# ContDet.net
KiCad netlist of a schematic drawn in EAGLE
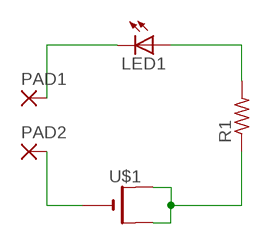
[diagram p0: schematic, sheet 1]

(export (version "E")
  (design (tool "Eeschema 10.0.6"))
  (components
    (comp (ref "LED1")
      (value "LEDCHIPLED_0805")
      (footprint "eagle-import:CHIPLED_0805")
      (libsource (lib "eagle-import") (part "LEDCHIPLED_0805"))
    )
    (comp (ref "PAD1")
      (value "SMD2")
      (footprint "eagle-import:SMD1,27-2,54")
      (libsource (lib "eagle-import") (part "SMD2"))
    )
    (comp (ref "PAD2")
      (value "SMD2")
      (footprint "eagle-import:SMD1,27-2,54")
      (libsource (lib "eagle-import") (part "SMD2"))
    )
    (comp (ref "R1")
      (value "R-US_FLIPFLOP")
      (footprint "eagle-import:0805-THM")
      (libsource (lib "eagle-import") (part "R-US_FLIPFLOP"))
    )
    (comp (ref "U$1")
      (value "CR1220SMT")
      (footprint "eagle-import:CR1220-SMD")
      (libsource (lib "eagle-import") (part "CR1220SMT"))
    )
  )
  (nets
    (net (code "1") (name "Net-(LED1-PadA)") (class "Default")
      (node (ref "LED1") (pin "A") (pinfunction "A_A") (pintype "passive"))
      (node (ref "R1") (pin "2") (pinfunction "2_2") (pintype "passive"))
    )
    (net (code "2") (name "Net-(PAD1-P)") (class "Default")
      (node (ref "LED1") (pin "C") (pinfunction "C_C") (pintype "passive"))
      (node (ref "PAD1") (pin "1") (pinfunction "P_1") (pintype "passive"))
    )
    (net (code "3") (name "Net-(PAD2-P)") (class "Default")
      (node (ref "PAD2") (pin "1") (pinfunction "P_1") (pintype "passive"))
      (node (ref "U$1") (pin "-") (pinfunction "-_-") (pintype "passive"))
    )
    (net (code "4") (name "Net-(U$1-+)") (class "Default")
      (node (ref "R1") (pin "1") (pinfunction "1_1") (pintype "passive"))
      (node (ref "U$1") (pin "+$1") (pinfunction "+_+$1") (pintype "passive"))
      (node (ref "U$1") (pin "+$2") (pinfunction "+1_+$2") (pintype "passive"))
    )
  )
)
